# PowerSupply.net
KiCad netlist of a schematic drawn in Altium Designer
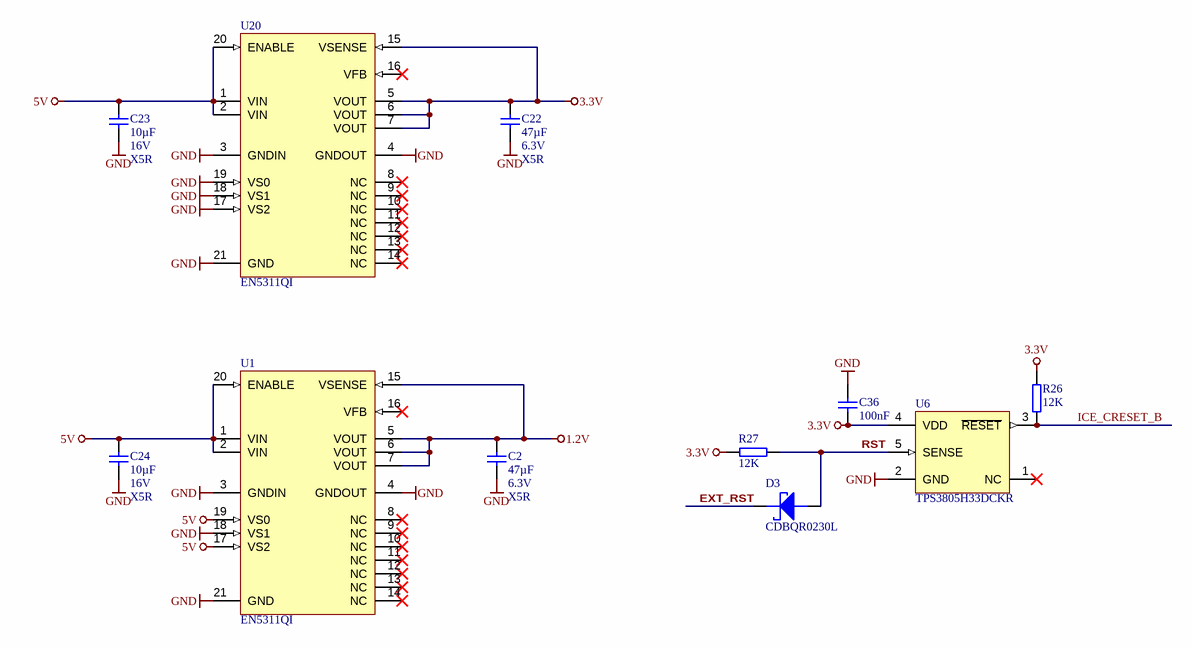
[diagram p0: PowerSupply.SchDoc]

(export (version "E")
  (design (tool "Eeschema 10.0.6"))
  (components
    (comp (ref "C2")
      (value "47µF")
      (footprint "CAPC2012X135N")
      (description "KON 47µF 6,3V  X5R SMD 20%")
      (fields
        (field (name "VOLTAGE") "6.3V")
        (field (name "TECHNOLOGY") "X5R")
        (field (name "TOLERANCE") "20%")
      )
      (libsource (lib "TE") (part "CAP-NP"))
    )
    (comp (ref "C22")
      (value "47µF")
      (footprint "CAPC2012X135N")
      (description "KON 47µF 6,3V  X5R SMD 20%")
      (fields
        (field (name "VOLTAGE") "6.3V")
        (field (name "TECHNOLOGY") "X5R")
        (field (name "TOLERANCE") "20%")
      )
      (libsource (lib "TE") (part "CAP-NP"))
    )
    (comp (ref "C23")
      (value "10µF")
      (footprint "CAPC1608X90N")
      (description "KON 10µF 16V X5R SMD 20%")
      (fields
        (field (name "VOLTAGE") "16V")
        (field (name "TECHNOLOGY") "X5R")
        (field (name "TOLERANCE") "20%")
      )
      (libsource (lib "TE") (part "CAP-NP"))
    )
    (comp (ref "C24")
      (value "10µF")
      (footprint "CAPC1608X90N")
      (description "KON 10µF 16V X5R SMD 20%")
      (fields
        (field (name "VOLTAGE") "16V")
        (field (name "TECHNOLOGY") "X5R")
        (field (name "TOLERANCE") "20%")
      )
      (libsource (lib "TE") (part "CAP-NP"))
    )
    (comp (ref "C36")
      (value "100nF")
      (footprint "CAPC1005X55N")
      (description "KON 100nF 50V SMD AEC-Q200")
      (fields (field (name "VOLTAGE") "50V") (field (name "TOLERANCE") "10%"))
      (libsource (lib "TE") (part "CAP-NP"))
    )
    (comp (ref "D3")
      (value "CDBQR0230L")
      (footprint "DIOC1006X55N")
      (fields (field (name "VOLTAGE") "0.2A"))
      (libsource (lib "TE") (part "SCHOTTKY"))
    )
    (comp (ref "R26")
      (value "12K")
      (footprint "RESC1005X40N")
      (description "WID SMD 12K 1% 0,063W")
      (libsource (lib "TE") (part "RES"))
    )
    (comp (ref "R27")
      (value "12K")
      (footprint "RESC1005X40N")
      (description "WID SMD 12K 1% 0,063W")
      (libsource (lib "TE") (part "RES"))
    )
    (comp (ref "U1") (value "EN5311QI") (footprint "EN5311QI") (libsource (lib "TE") (part "EN5311QI")))
    (comp (ref "U6")
      (value "TPS3805H33DCKR")
      (footprint "SOT65P210X110-5N")
      (libsource (lib "TE") (part "TPS3805H33DCK"))
    )
    (comp (ref "U20") (value "EN5311QI") (footprint "EN5311QI") (libsource (lib "TE") (part "EN5311QI")))
  )
  (nets
    (net (code "1") (name "/EXT_RST") (class "Default")
      (node (ref "D3") (pin "1") (pinfunction "KATHODE_1") (pintype "passive"))
    )
    (net (code "2") (name "/ICE_CRESET_B") (class "Default")
      (node (ref "R26") (pin "1") (pinfunction "1_1") (pintype "passive"))
      (node (ref "U6") (pin "3") (pinfunction "~{RESET}_3") (pintype "output"))
    )
    (net (code "3") (name "/RST") (class "Default")
      (node (ref "D3") (pin "2") (pinfunction "ANODE_2") (pintype "passive"))
      (node (ref "R27") (pin "1") (pinfunction "1_1") (pintype "passive"))
      (node (ref "U6") (pin "5") (pinfunction "SENSE_5") (pintype "input"))
    )
    (net (code "4") (name "1.2V") (class "Default")
      (node (ref "C2") (pin "2") (pinfunction "2_2") (pintype "passive"))
      (node (ref "U1") (pin "15") (pinfunction "VSENSE_15") (pintype "input"))
      (node (ref "U1") (pin "5") (pinfunction "VOUT_5") (pintype "power_in"))
      (node (ref "U1") (pin "6") (pinfunction "VOUT_6") (pintype "power_in"))
      (node (ref "U1") (pin "7") (pinfunction "VOUT_7") (pintype "power_in"))
    )
    (net (code "5") (name "3.3V") (class "Default")
      (node (ref "C22") (pin "2") (pinfunction "2_2") (pintype "passive"))
      (node (ref "C36") (pin "2") (pinfunction "2_2") (pintype "passive"))
      (node (ref "R26") (pin "2") (pinfunction "2_2") (pintype "passive"))
      (node (ref "R27") (pin "2") (pinfunction "2_2") (pintype "passive"))
      (node (ref "U20") (pin "15") (pinfunction "VSENSE_15") (pintype "input"))
      (node (ref "U20") (pin "5") (pinfunction "VOUT_5") (pintype "power_in"))
      (node (ref "U20") (pin "6") (pinfunction "VOUT_6") (pintype "power_in"))
      (node (ref "U20") (pin "7") (pinfunction "VOUT_7") (pintype "power_in"))
      (node (ref "U6") (pin "4") (pinfunction "VDD_4") (pintype "power_in"))
    )
    (net (code "6") (name "5V") (class "Default")
      (node (ref "C23") (pin "1") (pinfunction "1_1") (pintype "passive"))
      (node (ref "C24") (pin "1") (pinfunction "1_1") (pintype "passive"))
      (node (ref "U1") (pin "1") (pinfunction "VIN_1") (pintype "power_in"))
      (node (ref "U1") (pin "17") (pinfunction "VS2_17") (pintype "input"))
      (node (ref "U1") (pin "19") (pinfunction "VS0_19") (pintype "input"))
      (node (ref "U1") (pin "2") (pinfunction "VIN_2") (pintype "power_in"))
      (node (ref "U1") (pin "20") (pinfunction "ENABLE_20") (pintype "input"))
      (node (ref "U20") (pin "1") (pinfunction "VIN_1") (pintype "power_in"))
      (node (ref "U20") (pin "2") (pinfunction "VIN_2") (pintype "power_in"))
      (node (ref "U20") (pin "20") (pinfunction "ENABLE_20") (pintype "input"))
    )
    (net (code "7") (name "GND") (class "Default")
      (node (ref "C2") (pin "1") (pinfunction "1_1") (pintype "passive"))
      (node (ref "C22") (pin "1") (pinfunction "1_1") (pintype "passive"))
      (node (ref "C23") (pin "2") (pinfunction "2_2") (pintype "passive"))
      (node (ref "C24") (pin "2") (pinfunction "2_2") (pintype "passive"))
      (node (ref "C36") (pin "1") (pinfunction "1_1") (pintype "passive"))
      (node (ref "U1") (pin "18") (pinfunction "VS1_18") (pintype "input"))
      (node (ref "U1") (pin "21") (pinfunction "GND_21") (pintype "power_in"))
      (node (ref "U1") (pin "3") (pinfunction "GNDIN_3") (pintype "power_in"))
      (node (ref "U1") (pin "4") (pinfunction "GNDOUT_4") (pintype "power_in"))
      (node (ref "U20") (pin "17") (pinfunction "VS2_17") (pintype "input"))
      (node (ref "U20") (pin "18") (pinfunction "VS1_18") (pintype "input"))
      (node (ref "U20") (pin "19") (pinfunction "VS0_19") (pintype "input"))
      (node (ref "U20") (pin "21") (pinfunction "GND_21") (pintype "power_in"))
      (node (ref "U20") (pin "3") (pinfunction "GNDIN_3") (pintype "power_in"))
      (node (ref "U20") (pin "4") (pinfunction "GNDOUT_4") (pintype "power_in"))
      (node (ref "U6") (pin "2") (pinfunction "GND_2") (pintype "power_in"))
    )
    (net (code "8") (name "unconnected-(U1-NC-Pad8)") (class "Default")
      (node (ref "U1") (pin "8") (pinfunction "NC_8") (pintype "passive+no_connect"))
    )
    (net (code "9") (name "unconnected-(U1-NC-Pad9)") (class "Default")
      (node (ref "U1") (pin "9") (pinfunction "NC_9") (pintype "passive+no_connect"))
    )
    (net (code "10") (name "unconnected-(U1-NC-Pad10)") (class "Default")
      (node (ref "U1") (pin "10") (pinfunction "NC_10") (pintype "passive+no_connect"))
    )
    (net (code "11") (name "unconnected-(U1-NC-Pad11)") (class "Default")
      (node (ref "U1") (pin "11") (pinfunction "NC_11") (pintype "passive+no_connect"))
    )
    (net (code "12") (name "unconnected-(U1-NC-Pad12)") (class "Default")
      (node (ref "U1") (pin "12") (pinfunction "NC_12") (pintype "passive+no_connect"))
    )
    (net (code "13") (name "unconnected-(U1-NC-Pad13)") (class "Default")
      (node (ref "U1") (pin "13") (pinfunction "NC_13") (pintype "passive+no_connect"))
    )
    (net (code "14") (name "unconnected-(U1-NC-Pad14)") (class "Default")
      (node (ref "U1") (pin "14") (pinfunction "NC_14") (pintype "passive+no_connect"))
    )
    (net (code "15") (name "unconnected-(U1-VFB-Pad16)") (class "Default")
      (node (ref "U1") (pin "16") (pinfunction "VFB_16") (pintype "input+no_connect"))
    )
    (net (code "16") (name "unconnected-(U6-NC-Pad1)") (class "Default")
      (node (ref "U6") (pin "1") (pinfunction "NC_1") (pintype "passive+no_connect"))
    )
    (net (code "17") (name "unconnected-(U20-NC-Pad8)") (class "Default")
      (node (ref "U20") (pin "8") (pinfunction "NC_8") (pintype "passive+no_connect"))
    )
    (net (code "18") (name "unconnected-(U20-NC-Pad9)") (class "Default")
      (node (ref "U20") (pin "9") (pinfunction "NC_9") (pintype "passive+no_connect"))
    )
    (net (code "19") (name "unconnected-(U20-NC-Pad10)") (class "Default")
      (node (ref "U20") (pin "10") (pinfunction "NC_10") (pintype "passive+no_connect"))
    )
    (net (code "20") (name "unconnected-(U20-NC-Pad11)") (class "Default")
      (node (ref "U20") (pin "11") (pinfunction "NC_11") (pintype "passive+no_connect"))
    )
    (net (code "21") (name "unconnected-(U20-NC-Pad12)") (class "Default")
      (node (ref "U20") (pin "12") (pinfunction "NC_12") (pintype "passive+no_connect"))
    )
    (net (code "22") (name "unconnected-(U20-NC-Pad13)") (class "Default")
      (node (ref "U20") (pin "13") (pinfunction "NC_13") (pintype "passive+no_connect"))
    )
    (net (code "23") (name "unconnected-(U20-NC-Pad14)") (class "Default")
      (node (ref "U20") (pin "14") (pinfunction "NC_14") (pintype "passive+no_connect"))
    )
    (net (code "24") (name "unconnected-(U20-VFB-Pad16)") (class "Default")
      (node (ref "U20") (pin "16") (pinfunction "VFB_16") (pintype "input+no_connect"))
    )
  )
)
